# buttons.net
KiCad netlist of a schematic drawn in EAGLE
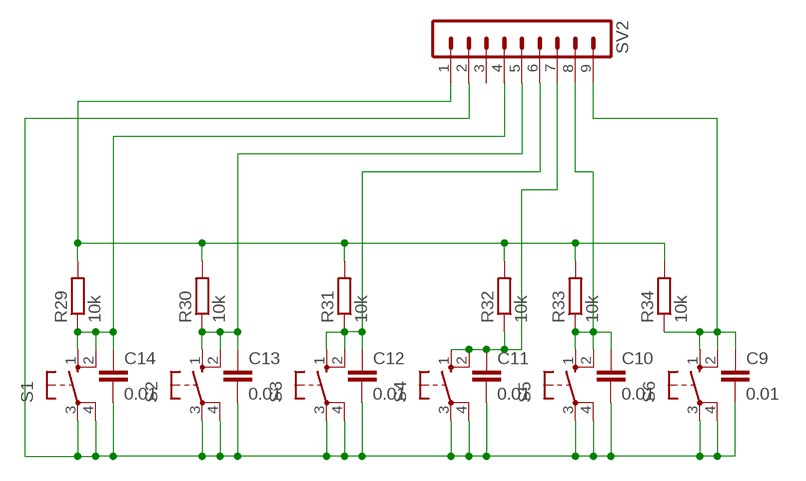
[diagram p0: schematic, sheet 1]

(export (version "E")
  (design (tool "Eeschema 10.0.6"))
  (components
    (comp (ref "C9")
      (value "0.01")
      (footprint "eagle-import:C0805")
      (libsource (lib "eagle-import") (part "C-EUC0805"))
    )
    (comp (ref "C10")
      (value "0.01")
      (footprint "eagle-import:C0805")
      (libsource (lib "eagle-import") (part "C-EUC0805"))
    )
    (comp (ref "C11")
      (value "0.01")
      (footprint "eagle-import:C0805")
      (libsource (lib "eagle-import") (part "C-EUC0805"))
    )
    (comp (ref "C12")
      (value "0.01")
      (footprint "eagle-import:C0805")
      (libsource (lib "eagle-import") (part "C-EUC0805"))
    )
    (comp (ref "C13")
      (value "0.01")
      (footprint "eagle-import:C0805")
      (libsource (lib "eagle-import") (part "C-EUC0805"))
    )
    (comp (ref "C14")
      (value "0.01")
      (footprint "eagle-import:C0805")
      (libsource (lib "eagle-import") (part "C-EUC0805"))
    )
    (comp (ref "R29")
      (value "10k")
      (footprint "eagle-import:R0805")
      (libsource (lib "eagle-import") (part "R-EU_R0805"))
    )
    (comp (ref "R30")
      (value "10k")
      (footprint "eagle-import:R0805")
      (libsource (lib "eagle-import") (part "R-EU_R0805"))
    )
    (comp (ref "R31")
      (value "10k")
      (footprint "eagle-import:R0805")
      (libsource (lib "eagle-import") (part "R-EU_R0805"))
    )
    (comp (ref "R32")
      (value "10k")
      (footprint "eagle-import:R0805")
      (libsource (lib "eagle-import") (part "R-EU_R0805"))
    )
    (comp (ref "R33")
      (value "10k")
      (footprint "eagle-import:R0805")
      (libsource (lib "eagle-import") (part "R-EU_R0805"))
    )
    (comp (ref "R34")
      (value "10k")
      (footprint "eagle-import:R0805")
      (libsource (lib "eagle-import") (part "R-EU_R0805"))
    )
    (comp (ref "S1")
      (value "40-XX")
      (footprint "eagle-import:B3F-40XX")
      (fields (field (name "MF") "OMRON COMPONENTS USA") (field (name "MPN") "B3F-4000"))
      (libsource (lib "eagle-import") (part "40-XX"))
    )
    (comp (ref "S2")
      (value "40-XX")
      (footprint "eagle-import:B3F-40XX")
      (fields (field (name "MF") "OMRON COMPONENTS USA") (field (name "MPN") "B3F-4000"))
      (libsource (lib "eagle-import") (part "40-XX"))
    )
    (comp (ref "S3")
      (value "40-XX")
      (footprint "eagle-import:B3F-40XX")
      (fields (field (name "MF") "OMRON COMPONENTS USA") (field (name "MPN") "B3F-4000"))
      (libsource (lib "eagle-import") (part "40-XX"))
    )
    (comp (ref "S4")
      (value "40-XX")
      (footprint "eagle-import:B3F-40XX")
      (fields (field (name "MF") "OMRON COMPONENTS USA") (field (name "MPN") "B3F-4000"))
      (libsource (lib "eagle-import") (part "40-XX"))
    )
    (comp (ref "S5")
      (value "40-XX")
      (footprint "eagle-import:B3F-40XX")
      (fields (field (name "MF") "OMRON COMPONENTS USA") (field (name "MPN") "B3F-4000"))
      (libsource (lib "eagle-import") (part "40-XX"))
    )
    (comp (ref "S6")
      (value "40-XX")
      (footprint "eagle-import:B3F-40XX")
      (fields (field (name "MF") "OMRON COMPONENTS USA") (field (name "MPN") "B3F-4000"))
      (libsource (lib "eagle-import") (part "40-XX"))
    )
    (comp (ref "SV2")
      (value "MA09-1")
      (footprint "eagle-import:MA09-1")
      (libsource (lib "eagle-import") (part "MA09-1"))
    )
  )
  (nets
    (net (code "1") (name "Net-(R29-Pad2)") (class "Default")
      (node (ref "R29") (pin "2") (pinfunction "2_2") (pintype "passive"))
      (node (ref "R30") (pin "2") (pinfunction "2_2") (pintype "passive"))
      (node (ref "R31") (pin "2") (pinfunction "2_2") (pintype "passive"))
      (node (ref "R32") (pin "2") (pinfunction "2_2") (pintype "passive"))
      (node (ref "R33") (pin "2") (pinfunction "2_2") (pintype "passive"))
      (node (ref "R34") (pin "2") (pinfunction "2_2") (pintype "passive"))
      (node (ref "SV2") (pin "1") (pinfunction "1_1") (pintype "passive"))
    )
    (net (code "2") (name "Net-(S1-P)") (class "Default")
      (node (ref "C10") (pin "2") (pinfunction "2_2") (pintype "passive"))
      (node (ref "C11") (pin "2") (pinfunction "2_2") (pintype "passive"))
      (node (ref "C12") (pin "2") (pinfunction "2_2") (pintype "passive"))
      (node (ref "C13") (pin "2") (pinfunction "2_2") (pintype "passive"))
      (node (ref "C14") (pin "2") (pinfunction "2_2") (pintype "passive"))
      (node (ref "C9") (pin "2") (pinfunction "2_2") (pintype "passive"))
      (node (ref "S1") (pin "3") (pinfunction "P_3") (pintype "passive"))
      (node (ref "S1") (pin "4") (pinfunction "P1_4") (pintype "passive"))
      (node (ref "S2") (pin "3") (pinfunction "P_3") (pintype "passive"))
      (node (ref "S2") (pin "4") (pinfunction "P1_4") (pintype "passive"))
      (node (ref "S3") (pin "3") (pinfunction "P_3") (pintype "passive"))
      (node (ref "S3") (pin "4") (pinfunction "P1_4") (pintype "passive"))
      (node (ref "S4") (pin "3") (pinfunction "P_3") (pintype "passive"))
      (node (ref "S4") (pin "4") (pinfunction "P1_4") (pintype "passive"))
      (node (ref "S5") (pin "3") (pinfunction "P_3") (pintype "passive"))
      (node (ref "S5") (pin "4") (pinfunction "P1_4") (pintype "passive"))
      (node (ref "S6") (pin "3") (pinfunction "P_3") (pintype "passive"))
      (node (ref "S6") (pin "4") (pinfunction "P1_4") (pintype "passive"))
      (node (ref "SV2") (pin "2") (pinfunction "2_2") (pintype "passive"))
    )
    (net (code "3") (name "Net-(S1-S)") (class "Default")
      (node (ref "C14") (pin "1") (pinfunction "1_1") (pintype "passive"))
      (node (ref "R29") (pin "1") (pinfunction "1_1") (pintype "passive"))
      (node (ref "S1") (pin "1") (pinfunction "S_1") (pintype "passive"))
      (node (ref "S1") (pin "2") (pinfunction "S1_2") (pintype "passive"))
      (node (ref "SV2") (pin "4") (pinfunction "4_4") (pintype "passive"))
    )
    (net (code "4") (name "Net-(S2-S)") (class "Default")
      (node (ref "C13") (pin "1") (pinfunction "1_1") (pintype "passive"))
      (node (ref "R30") (pin "1") (pinfunction "1_1") (pintype "passive"))
      (node (ref "S2") (pin "1") (pinfunction "S_1") (pintype "passive"))
      (node (ref "S2") (pin "2") (pinfunction "S1_2") (pintype "passive"))
      (node (ref "SV2") (pin "5") (pinfunction "5_5") (pintype "passive"))
    )
    (net (code "5") (name "Net-(S3-S)") (class "Default")
      (node (ref "C12") (pin "1") (pinfunction "1_1") (pintype "passive"))
      (node (ref "R31") (pin "1") (pinfunction "1_1") (pintype "passive"))
      (node (ref "S3") (pin "1") (pinfunction "S_1") (pintype "passive"))
      (node (ref "S3") (pin "2") (pinfunction "S1_2") (pintype "passive"))
      (node (ref "SV2") (pin "6") (pinfunction "6_6") (pintype "passive"))
    )
    (net (code "6") (name "Net-(S4-S)") (class "Default")
      (node (ref "C11") (pin "1") (pinfunction "1_1") (pintype "passive"))
      (node (ref "R32") (pin "1") (pinfunction "1_1") (pintype "passive"))
      (node (ref "S4") (pin "1") (pinfunction "S_1") (pintype "passive"))
      (node (ref "S4") (pin "2") (pinfunction "S1_2") (pintype "passive"))
      (node (ref "SV2") (pin "7") (pinfunction "7_7") (pintype "passive"))
    )
    (net (code "7") (name "Net-(S5-S)") (class "Default")
      (node (ref "C10") (pin "1") (pinfunction "1_1") (pintype "passive"))
      (node (ref "R33") (pin "1") (pinfunction "1_1") (pintype "passive"))
      (node (ref "S5") (pin "1") (pinfunction "S_1") (pintype "passive"))
      (node (ref "S5") (pin "2") (pinfunction "S1_2") (pintype "passive"))
      (node (ref "SV2") (pin "8") (pinfunction "8_8") (pintype "passive"))
    )
    (net (code "8") (name "Net-(S6-S)") (class "Default")
      (node (ref "C9") (pin "1") (pinfunction "1_1") (pintype "passive"))
      (node (ref "R34") (pin "1") (pinfunction "1_1") (pintype "passive"))
      (node (ref "S6") (pin "1") (pinfunction "S_1") (pintype "passive"))
      (node (ref "S6") (pin "2") (pinfunction "S1_2") (pintype "passive"))
      (node (ref "SV2") (pin "9") (pinfunction "9_9") (pintype "passive"))
    )
    (net (code "9") (name "unconnected-(SV2-Pad3)") (class "Default")
      (node (ref "SV2") (pin "3") (pinfunction "3_3") (pintype "passive"))
    )
  )
)
